# Sch_loapay.net
KiCad netlist of a schematic drawn in Altium Designer
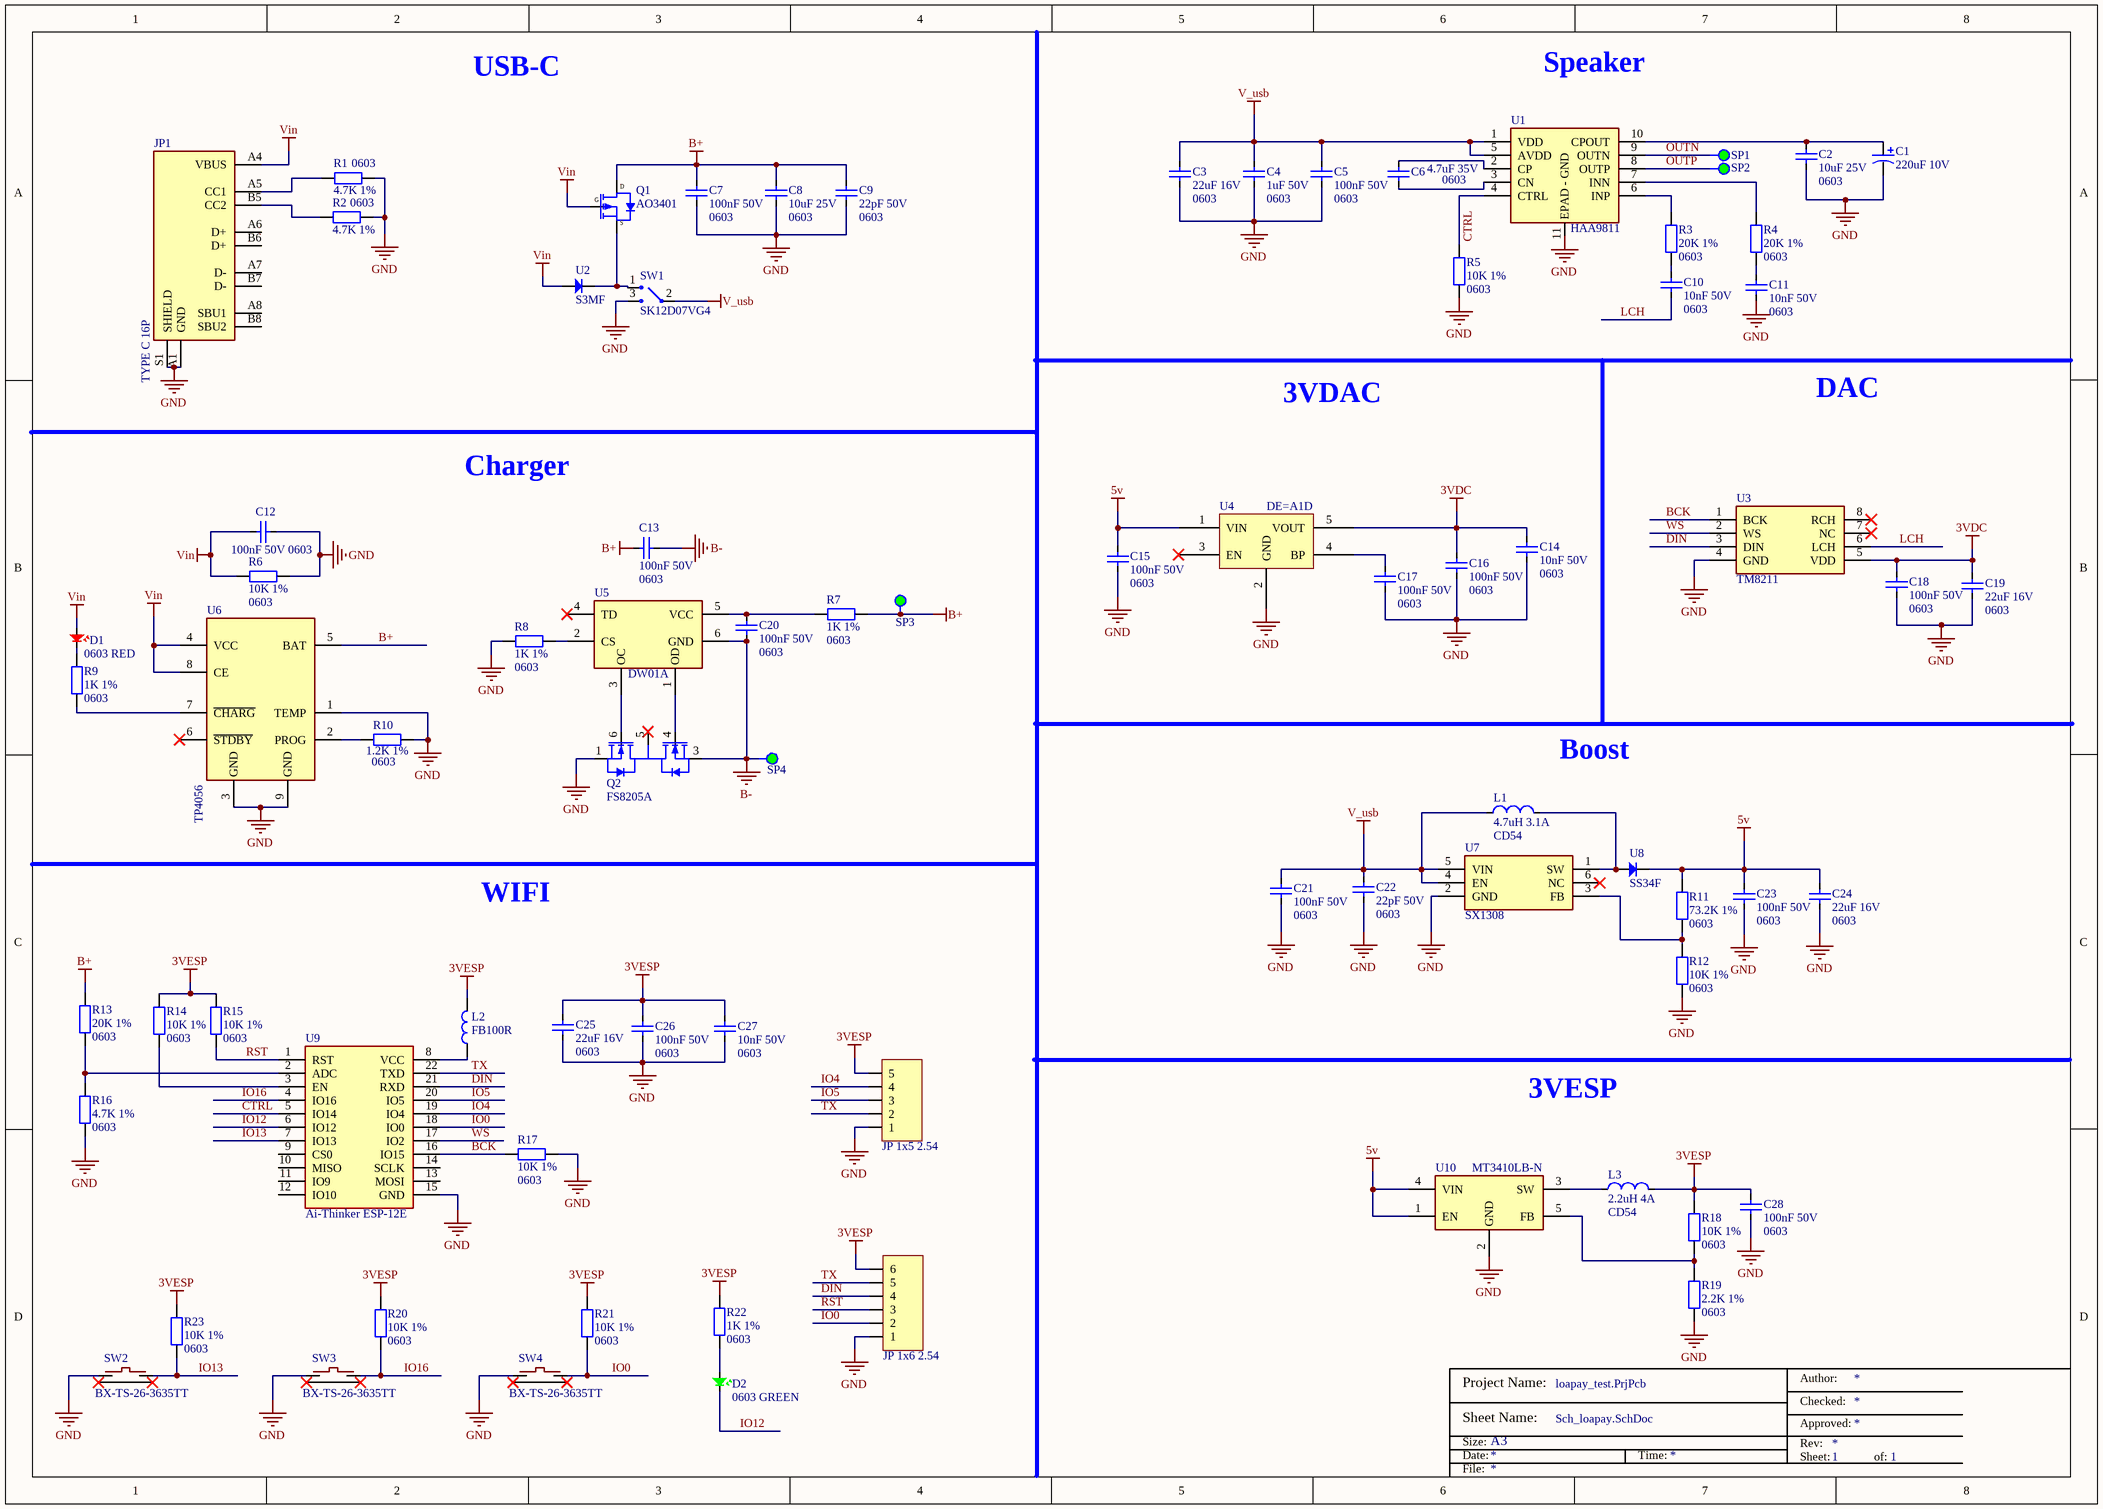
[diagram p0: Sch_loapay.SchDoc]

(export (version "E")
  (design (tool "Eeschema 10.0.6"))
  (components
    (comp (ref "C1")
      (value "220uF 10V")
      (footprint "CAP-ALU-SMD-D-NEW")
      (description "220uF 10V ±20% SMD,D6.3xL7.7mm Aluminum Electrolytic Capacitors - SMD ROHS")
      (fields
        (field (name "MANUFACTURER") "Honor Elec")
        (field (name "MANUFACTURE PART NUMBER") "RVT1A221M0607")
      )
      (libsource (lib "IOT SOLUTIONS LOAPAY V5.5.2") (part "C_ALU_220uF_10V_D"))
    )
    (comp (ref "C2")
      (value "10uF 25V")
      (footprint "C0603")
      (description "25V 10uF X5R ±10% 0603 Multilayer Ceramic Capacitors MLCC - SMD/SMT ROHS")
      (fields
        (field (name "MANUFACTURER") "Murata Electronics")
        (field (name "MANUFACTURE PART NUMBER") "GRM188R61E106KA73D")
        (field (name "PACKAGE") "0603")
      )
      (libsource (lib "IOT SOLUTIONS LOAPAY V5.5.2") (part "C0603_MLCC_10uF_25V"))
    )
    (comp (ref "C3")
      (value "22uF 16V")
      (footprint "C0603")
      (description "16V 22uF X5R ±20% 0603 Multilayer Ceramic Capacitors MLCC - SMD/SMT ROHS")
      (fields
        (field (name "MANUFACTURER") "Samsung Electro-Mechanics")
        (field (name "MANUFACTURE PART NUMBER") "CL10A226MO7JZNC")
        (field (name "PACKAGE") "0603")
      )
      (libsource (lib "IOT SOLUTIONS LOAPAY V5.5.2") (part "C0603_MLCC_22uF_16V"))
    )
    (comp (ref "C4")
      (value "1uF 50V")
      (footprint "C0603")
      (description "1 µF ±10% 50V Ceramic Capacitor X5R 0603 (1608 Metric)")
      (fields
        (field (name "MANUFACTURER") "Murata Electronics")
        (field (name "MANUFACTURE PART NUMBER") "GRT188R61H105KE13D")
        (field (name "PACKAGE") "0603")
      )
      (libsource (lib "IOT SOLUTIONS LOAPAY V5.5.2") (part "C0603_MLCC_1uF_50V"))
    )
    (comp (ref "C5")
      (value "100nF 50V")
      (footprint "C0603")
      (description "50V 100nF X7R ±10% 0603 Multilayer Ceramic Capacitors MLCC - SMD/SMT ROHS")
      (fields
        (field (name "MANUFACTURER") "YAGEO")
        (field (name "MANUFACTURE PART NUMBER") "CC0603KRX7R9BB104")
        (field (name "PACKAGE") "0603")
      )
      (libsource (lib "IOT SOLUTIONS LOAPAY V5.5.2") (part "C0603_MLCC_100nF_50V"))
    )
    (comp (ref "C6")
      (value "4.7uF 35V")
      (footprint "C0603")
      (description "35V 4.7uF X5R ±10% 0603 Multilayer Ceramic Capacitors MLCC - SMD/SMT ROHS")
      (fields
        (field (name "MANUFACTURER") "TDK")
        (field (name "MANUFACTURE PART NUMBER") "C1608X5R1V475KT000E")
        (field (name "PACKAGE") "0603")
      )
      (libsource (lib "IOT SOLUTIONS LOAPAY V5.5.2") (part "C0603_MLCC_4.7uF_35V"))
    )
    (comp (ref "C7")
      (value "100nF 50V")
      (footprint "C0603")
      (description "50V 100nF X7R ±10% 0603 Multilayer Ceramic Capacitors MLCC - SMD/SMT ROHS")
      (fields
        (field (name "MANUFACTURER") "YAGEO")
        (field (name "MANUFACTURE PART NUMBER") "CC0603KRX7R9BB104")
        (field (name "PACKAGE") "0603")
      )
      (libsource (lib "IOT SOLUTIONS LOAPAY V5.5.2") (part "C0603_MLCC_100nF_50V"))
    )
    (comp (ref "C8")
      (value "10uF 25V")
      (footprint "C0603")
      (description "25V 10uF X5R ±10% 0603 Multilayer Ceramic Capacitors MLCC - SMD/SMT ROHS")
      (fields
        (field (name "MANUFACTURER") "Murata Electronics")
        (field (name "MANUFACTURE PART NUMBER") "GRM188R61E106KA73D")
        (field (name "PACKAGE") "0603")
      )
      (libsource (lib "IOT SOLUTIONS LOAPAY V5.5.2") (part "C0603_MLCC_10uF_25V"))
    )
    (comp (ref "C9")
      (value "22pF 50V")
      (footprint "C0603")
      (description "50V 22pF NP0 ±5% 0603 Multilayer Ceramic Capacitors MLCC - SMD/SMT ROHS")
      (fields
        (field (name "MANUFACTURER") "YAGEO")
        (field (name "MANUFACTURE PART NUMBER") "CC0603JRNPO9BN220")
        (field (name "PACKAGE") "0603")
      )
      (libsource (lib "IOT SOLUTIONS LOAPAY V5.5.2") (part "C0603_MLCC_22pF_50V"))
    )
    (comp (ref "C10")
      (value "10nF 50V")
      (footprint "C0603")
      (description "50V 10nF X7R ±10% 0603 Multilayer Ceramic Capacitors MLCC - SMD/SMT ROHS")
      (fields
        (field (name "MANUFACTURER") "YAGEO")
        (field (name "MANUFACTURE PART NUMBER") "CC0603KRX7R9BB103")
        (field (name "PACKAGE") "0603")
      )
      (libsource (lib "IOT SOLUTIONS LOAPAY V5.5.2") (part "C0603_MLCC_10nF_50V"))
    )
    (comp (ref "C11")
      (value "10nF 50V")
      (footprint "C0603")
      (description "50V 10nF X7R ±10% 0603 Multilayer Ceramic Capacitors MLCC - SMD/SMT ROHS")
      (fields
        (field (name "MANUFACTURER") "YAGEO")
        (field (name "MANUFACTURE PART NUMBER") "CC0603KRX7R9BB103")
        (field (name "PACKAGE") "0603")
      )
      (libsource (lib "IOT SOLUTIONS LOAPAY V5.5.2") (part "C0603_MLCC_10nF_50V"))
    )
    (comp (ref "C12")
      (value "100nF 50V")
      (footprint "C0603")
      (description "50V 100nF X7R ±10% 0603 Multilayer Ceramic Capacitors MLCC - SMD/SMT ROHS")
      (fields
        (field (name "MANUFACTURER") "YAGEO")
        (field (name "MANUFACTURE PART NUMBER") "CC0603KRX7R9BB104")
        (field (name "PACKAGE") "0603")
      )
      (libsource (lib "IOT SOLUTIONS LOAPAY V5.5.2") (part "C0603_MLCC_100nF_50V"))
    )
    (comp (ref "C13")
      (value "100nF 50V")
      (footprint "C0603")
      (description "50V 100nF X7R ±10% 0603 Multilayer Ceramic Capacitors MLCC - SMD/SMT ROHS")
      (fields
        (field (name "MANUFACTURER") "YAGEO")
        (field (name "MANUFACTURE PART NUMBER") "CC0603KRX7R9BB104")
        (field (name "PACKAGE") "0603")
      )
      (libsource (lib "IOT SOLUTIONS LOAPAY V5.5.2") (part "C0603_MLCC_100nF_50V"))
    )
    (comp (ref "C14")
      (value "10nF 50V")
      (footprint "C0603")
      (description "50V 10nF X7R ±10% 0603 Multilayer Ceramic Capacitors MLCC - SMD/SMT ROHS")
      (fields
        (field (name "MANUFACTURER") "YAGEO")
        (field (name "MANUFACTURE PART NUMBER") "CC0603KRX7R9BB103")
        (field (name "PACKAGE") "0603")
      )
      (libsource (lib "IOT SOLUTIONS LOAPAY V5.5.2") (part "C0603_MLCC_10nF_50V"))
    )
    (comp (ref "C15")
      (value "100nF 50V")
      (footprint "C0603")
      (description "50V 100nF X7R ±10% 0603 Multilayer Ceramic Capacitors MLCC - SMD/SMT ROHS")
      (fields
        (field (name "MANUFACTURER") "YAGEO")
        (field (name "MANUFACTURE PART NUMBER") "CC0603KRX7R9BB104")
        (field (name "PACKAGE") "0603")
      )
      (libsource (lib "IOT SOLUTIONS LOAPAY V5.5.2") (part "C0603_MLCC_100nF_50V"))
    )
    (comp (ref "C16")
      (value "100nF 50V")
      (footprint "C0603")
      (description "50V 100nF X7R ±10% 0603 Multilayer Ceramic Capacitors MLCC - SMD/SMT ROHS")
      (fields
        (field (name "MANUFACTURER") "YAGEO")
        (field (name "MANUFACTURE PART NUMBER") "CC0603KRX7R9BB104")
        (field (name "PACKAGE") "0603")
      )
      (libsource (lib "IOT SOLUTIONS LOAPAY V5.5.2") (part "C0603_MLCC_100nF_50V"))
    )
    (comp (ref "C17")
      (value "100nF 50V")
      (footprint "C0603")
      (description "50V 100nF X7R ±10% 0603 Multilayer Ceramic Capacitors MLCC - SMD/SMT ROHS")
      (fields
        (field (name "MANUFACTURER") "YAGEO")
        (field (name "MANUFACTURE PART NUMBER") "CC0603KRX7R9BB104")
        (field (name "PACKAGE") "0603")
      )
      (libsource (lib "IOT SOLUTIONS LOAPAY V5.5.2") (part "C0603_MLCC_100nF_50V"))
    )
    (comp (ref "C18")
      (value "100nF 50V")
      (footprint "C0603")
      (description "50V 100nF X7R ±10% 0603 Multilayer Ceramic Capacitors MLCC - SMD/SMT ROHS")
      (fields
        (field (name "MANUFACTURER") "YAGEO")
        (field (name "MANUFACTURE PART NUMBER") "CC0603KRX7R9BB104")
        (field (name "PACKAGE") "0603")
      )
      (libsource (lib "IOT SOLUTIONS LOAPAY V5.5.2") (part "C0603_MLCC_100nF_50V"))
    )
    (comp (ref "C19")
      (value "22uF 16V")
      (footprint "C0603")
      (description "16V 22uF X5R ±20% 0603 Multilayer Ceramic Capacitors MLCC - SMD/SMT ROHS")
      (fields
        (field (name "MANUFACTURER") "Samsung Electro-Mechanics")
        (field (name "MANUFACTURE PART NUMBER") "CL10A226MO7JZNC")
        (field (name "PACKAGE") "0603")
      )
      (libsource (lib "IOT SOLUTIONS LOAPAY V5.5.2") (part "C0603_MLCC_22uF_16V"))
    )
    (comp (ref "C20")
      (value "100nF 50V")
      (footprint "C0603")
      (description "50V 100nF X7R ±10% 0603 Multilayer Ceramic Capacitors MLCC - SMD/SMT ROHS")
      (fields
        (field (name "MANUFACTURER") "YAGEO")
        (field (name "MANUFACTURE PART NUMBER") "CC0603KRX7R9BB104")
        (field (name "PACKAGE") "0603")
      )
      (libsource (lib "IOT SOLUTIONS LOAPAY V5.5.2") (part "C0603_MLCC_100nF_50V"))
    )
    (comp (ref "C21")
      (value "100nF 50V")
      (footprint "C0603")
      (description "50V 100nF X7R ±10% 0603 Multilayer Ceramic Capacitors MLCC - SMD/SMT ROHS")
      (fields
        (field (name "MANUFACTURER") "YAGEO")
        (field (name "MANUFACTURE PART NUMBER") "CC0603KRX7R9BB104")
        (field (name "PACKAGE") "0603")
      )
      (libsource (lib "IOT SOLUTIONS LOAPAY V5.5.2") (part "C0603_MLCC_100nF_50V"))
    )
    (comp (ref "C22")
      (value "22pF 50V")
      (footprint "C0603")
      (description "50V 22pF NP0 ±5% 0603 Multilayer Ceramic Capacitors MLCC - SMD/SMT ROHS")
      (fields
        (field (name "MANUFACTURER") "YAGEO")
        (field (name "MANUFACTURE PART NUMBER") "CC0603JRNPO9BN220")
        (field (name "PACKAGE") "0603")
      )
      (libsource (lib "IOT SOLUTIONS LOAPAY V5.5.2") (part "C0603_MLCC_22pF_50V"))
    )
    (comp (ref "C23")
      (value "100nF 50V")
      (footprint "C0603")
      (description "50V 100nF X7R ±10% 0603 Multilayer Ceramic Capacitors MLCC - SMD/SMT ROHS")
      (fields
        (field (name "MANUFACTURER") "YAGEO")
        (field (name "MANUFACTURE PART NUMBER") "CC0603KRX7R9BB104")
        (field (name "PACKAGE") "0603")
      )
      (libsource (lib "IOT SOLUTIONS LOAPAY V5.5.2") (part "C0603_MLCC_100nF_50V"))
    )
    (comp (ref "C24")
      (value "22uF 16V")
      (footprint "C0603")
      (description "16V 22uF X5R ±20% 0603 Multilayer Ceramic Capacitors MLCC - SMD/SMT ROHS")
      (fields
        (field (name "MANUFACTURER") "Samsung Electro-Mechanics")
        (field (name "MANUFACTURE PART NUMBER") "CL10A226MO7JZNC")
        (field (name "PACKAGE") "0603")
      )
      (libsource (lib "IOT SOLUTIONS LOAPAY V5.5.2") (part "C0603_MLCC_22uF_16V"))
    )
    (comp (ref "C25")
      (value "22uF 16V")
      (footprint "C0603")
      (description "16V 22uF X5R ±20% 0603 Multilayer Ceramic Capacitors MLCC - SMD/SMT ROHS")
      (fields
        (field (name "MANUFACTURER") "Samsung Electro-Mechanics")
        (field (name "MANUFACTURE PART NUMBER") "CL10A226MO7JZNC")
        (field (name "PACKAGE") "0603")
      )
      (libsource (lib "IOT SOLUTIONS LOAPAY V5.5.2") (part "C0603_MLCC_22uF_16V"))
    )
    (comp (ref "C26")
      (value "100nF 50V")
      (footprint "C0603")
      (description "50V 100nF X7R ±10% 0603 Multilayer Ceramic Capacitors MLCC - SMD/SMT ROHS")
      (fields
        (field (name "MANUFACTURER") "YAGEO")
        (field (name "MANUFACTURE PART NUMBER") "CC0603KRX7R9BB104")
        (field (name "PACKAGE") "0603")
      )
      (libsource (lib "IOT SOLUTIONS LOAPAY V5.5.2") (part "C0603_MLCC_100nF_50V"))
    )
    (comp (ref "C27")
      (value "10nF 50V")
      (footprint "C0603")
      (description "50V 10nF X7R ±10% 0603 Multilayer Ceramic Capacitors MLCC - SMD/SMT ROHS")
      (fields
        (field (name "MANUFACTURER") "YAGEO")
        (field (name "MANUFACTURE PART NUMBER") "CC0603KRX7R9BB103")
        (field (name "PACKAGE") "0603")
      )
      (libsource (lib "IOT SOLUTIONS LOAPAY V5.5.2") (part "C0603_MLCC_10nF_50V"))
    )
    (comp (ref "C28")
      (value "100nF 50V")
      (footprint "C0603")
      (description "50V 100nF X7R ±10% 0603 Multilayer Ceramic Capacitors MLCC - SMD/SMT ROHS")
      (fields
        (field (name "MANUFACTURER") "YAGEO")
        (field (name "MANUFACTURE PART NUMBER") "CC0603KRX7R9BB104")
        (field (name "PACKAGE") "0603")
      )
      (libsource (lib "IOT SOLUTIONS LOAPAY V5.5.2") (part "C0603_MLCC_100nF_50V"))
    )
    (comp (ref "D1")
      (value "0603 RED")
      (footprint "LED0603_RED")
      (fields
        (field (name "MANUFACTURER") "XINGLIGHT")
        (field (name "MANUFACTURE PART NUMBER") "XL-1608SURC-06")
      )
      (libsource (lib "IOT SOLUTIONS LOAPAY V5.5.2") (part "L0603_RED"))
    )
    (comp (ref "D2")
      (value "0603 GREEN")
      (footprint "LED0603_GREEN")
      (fields
        (field (name "MANUFACTURER") "Amicc")
        (field (name "MANUFACTURE PART NUMBER") "A-SP192DGHC-C01-4T")
      )
      (libsource (lib "IOT SOLUTIONS LOAPAY V5.5.2") (part "L0603_GREEN"))
    )
    (comp (ref "JP1")
      (value "TYPE C 16P")
      (footprint "TYPE C 16P")
      (fields
        (field (name "MANUFACTURER") "Amphenol ICC (Commercial Products)")
        (field (name "MANUFACTURE PART NUMBER") "12402012E212A")
      )
      (libsource (lib "IOT SOLUTIONS LOAPAY V5.5.2") (part "TYPE_C_16P"))
    )
    (comp (ref "JP2")
      (value "JP 1x5 2.54")
      (footprint "JP 1x5 DT")
      (description "Cắm")
      (libsource (lib "Altium_Lib_by_KhueNguyenCreator") (part "JP 1x5 2.54 Duc Thang"))
    )
    (comp (ref "JP3")
      (value "JP 1x6 2.54")
      (footprint "JP 1x6 DT")
      (description "Cắm")
      (libsource (lib "Altium_Lib_by_KhueNguyenCreator") (part "JP 1x6 2.54 Duc Thang"))
    )
    (comp (ref "L1")
      (value "4.7uH 3.1A")
      (footprint "CD54")
      (description "3.1A 4.7uH ±20% SMD,5.8x5.2mm Power Inductors ROHS")
      (fields
        (field (name "MANUFACTURER") "Ceaiya")
        (field (name "MANUFACTURE PART NUMBER") "CD54-4R7M")
        (field (name "PACKAGE") "CD54")
      )
      (libsource (lib "IOT SOLUTIONS LOAPAY V5.5.2") (part "CD54_4.7uH_3.1A"))
    )
    (comp (ref "L2")
      (value "FB100R")
      (footprint "L-INDUCTOR 1206")
      (libsource (lib "IO84C124LR") (part "L-Inductor"))
    )
    (comp (ref "L3")
      (value "2.2uH 4A")
      (footprint "CD54")
      (description "4A 2.2uH ±20% SMD,5.8x5.2mm Power Inductors ROHS")
      (fields
        (field (name "MANUFACTURER") "Ceaiya")
        (field (name "MANUFACTURE PART NUMBER") "CD54-2R2M")
        (field (name "PACKAGE") "CD54")
      )
      (libsource (lib "IOT SOLUTIONS LOAPAY V5.5.2") (part "CD54_2.2uH_4A"))
    )
    (comp (ref "Q1")
      (value "AO3401")
      (footprint "SOT-23-3")
      (description "30V 4.2A 42mΩ@10V,4A 1.4W 800mV@250uA 1 Piece P-Channel SOT-23 MOSFETs ROHS")
      (fields (field (name "MANUFACTURER") "ElecSuper"))
      (libsource (lib "IOT SOLUTIONS LOAPAY V5.5.2") (part "AO3401"))
    )
    (comp (ref "Q2")
      (value "FS8205A")
      (footprint "SOT23-6")
      (description "20V 25mΩ@2.5V,3A 1.5W 500mV SOT-23-6 MOSFETs ROHS")
      (fields (field (name "MANUFACTURER") "TECH PUBLIC"))
      (libsource (lib "IOT SOLUTIONS LOAPAY V5.5.2") (part "FS8205A"))
    )
    (comp (ref "R1")
      (value "4.7K 1%")
      (footprint "RES_SMD_0603")
      (description "4.7 kOhms ±1% 0.1W, 1/10W Chip Resistor 0603 (1608 Metric) Moisture Resistant Thick Film")
      (fields
        (field (name "MANUFACTURER") "YAGEO")
        (field (name "MANUFACTURE PART NUMBER") "RC0603FR-074K7L")
        (field (name "PACKAGE") "0603")
      )
      (libsource (lib "IOT SOLUTIONS LOAPAY V5.5.2") (part "R0603_4.7K"))
    )
    (comp (ref "R2")
      (value "4.7K 1%")
      (footprint "RES_SMD_0603")
      (description "4.7 kOhms ±1% 0.1W, 1/10W Chip Resistor 0603 (1608 Metric) Moisture Resistant Thick Film")
      (fields
        (field (name "MANUFACTURER") "YAGEO")
        (field (name "MANUFACTURE PART NUMBER") "RC0603FR-074K7L")
        (field (name "PACKAGE") "0603")
      )
      (libsource (lib "IOT SOLUTIONS LOAPAY V5.5.2") (part "R0603_4.7K"))
    )
    (comp (ref "R3")
      (value "20K 1%")
      (footprint "RES_SMD_0603")
      (description "20 kOhms ±1% 0.063W, 1/16W Chip Resistor 0402 (1005 Metric) Moisture Resistant Thick Film")
      (fields
        (field (name "MANUFACTURER") "YAGEO")
        (field (name "MANUFACTURE PART NUMBER") "RC0805FR-0720KL")
        (field (name "PACKAGE") "0603")
      )
      (libsource (lib "IOT SOLUTIONS LOAPAY V5.5.2") (part "R0603_20K"))
    )
    (comp (ref "R4")
      (value "20K 1%")
      (footprint "RES_SMD_0603")
      (description "20 kOhms ±1% 0.063W, 1/16W Chip Resistor 0402 (1005 Metric) Moisture Resistant Thick Film")
      (fields
        (field (name "MANUFACTURER") "YAGEO")
        (field (name "MANUFACTURE PART NUMBER") "RC0805FR-0720KL")
        (field (name "PACKAGE") "0603")
      )
      (libsource (lib "IOT SOLUTIONS LOAPAY V5.5.2") (part "R0603_20K"))
    )
    (comp (ref "R5")
      (value "10K 1%")
      (footprint "RES_SMD_0603")
      (description "10 kOhms ±1% 0.1W, 1/10W Chip Resistor 0603 (1608 Metric) Moisture Resistant Thick Film")
      (fields
        (field (name "MANUFACTURER") "YAGEO")
        (field (name "MANUFACTURE PART NUMBER") "RC0603FR-0710KL")
        (field (name "PACKAGE") "0603")
      )
      (libsource (lib "IOT SOLUTIONS LOAPAY V5.5.2") (part "R0603_10K"))
    )
    (comp (ref "R6")
      (value "10K 1%")
      (footprint "RES_SMD_0603")
      (description "10 kOhms ±1% 0.1W, 1/10W Chip Resistor 0603 (1608 Metric) Moisture Resistant Thick Film")
      (fields
        (field (name "MANUFACTURER") "YAGEO")
        (field (name "MANUFACTURE PART NUMBER") "RC0603FR-0710KL")
        (field (name "PACKAGE") "0603")
      )
      (libsource (lib "IOT SOLUTIONS LOAPAY V5.5.2") (part "R0603_10K"))
    )
    (comp (ref "R7")
      (value "1K 1%")
      (footprint "RES_SMD_0603")
      (description "1 kOhms ±1% 0.1W, 1/10W Chip Resistor 0603 (1608 Metric) Moisture Resistant Thick Film")
      (fields
        (field (name "MANUFACTURER") "YAGEO")
        (field (name "MANUFACTURE PART NUMBER") "RC0603FR-071KL")
        (field (name "PACKAGE") "0603")
      )
      (libsource (lib "IOT SOLUTIONS LOAPAY V5.5.2") (part "R0603_1K"))
    )
    (comp (ref "R8")
      (value "1K 1%")
      (footprint "RES_SMD_0603")
      (description "1 kOhms ±1% 0.1W, 1/10W Chip Resistor 0603 (1608 Metric) Moisture Resistant Thick Film")
      (fields
        (field (name "MANUFACTURER") "YAGEO")
        (field (name "MANUFACTURE PART NUMBER") "RC0603FR-071KL")
        (field (name "PACKAGE") "0603")
      )
      (libsource (lib "IOT SOLUTIONS LOAPAY V5.5.2") (part "R0603_1K"))
    )
    (comp (ref "R9")
      (value "1K 1%")
      (footprint "RES_SMD_0603")
      (description "1 kOhms ±1% 0.1W, 1/10W Chip Resistor 0603 (1608 Metric) Moisture Resistant Thick Film")
      (fields
        (field (name "MANUFACTURER") "YAGEO")
        (field (name "MANUFACTURE PART NUMBER") "RC0603FR-071KL")
        (field (name "PACKAGE") "0603")
      )
      (libsource (lib "IOT SOLUTIONS LOAPAY V5.5.2") (part "R0603_1K"))
    )
    (comp (ref "R10")
      (value "1.2K 1%")
      (footprint "RES_SMD_0603")
      (description "1.2 kOhms ±1% 0.1W, 1/10W Chip Resistor 0603 (1608 Metric) Moisture Resistant Thick Film")
      (fields
        (field (name "MANUFACTURER") "YAGEO")
        (field (name "MANUFACTURE PART NUMBER") "RC0603FR-071K2L")
        (field (name "PACKAGE") "0603")
      )
      (libsource (lib "IOT SOLUTIONS LOAPAY V5.5.2") (part "R0603_1.2K"))
    )
    (comp (ref "R11")
      (value "73.2K 1%")
      (footprint "RES_SMD_0603")
      (description "73.2 kOhms ±1% 0.1W, 1/10W Chip Resistor 0603 (1608 Metric) Moisture Resistant Thick Film")
      (fields
        (field (name "MANUFACTURER") "YAGEO")
        (field (name "MANUFACTURE PART NUMBER") "RC0603FR-0773K2L")
        (field (name "PACKAGE") "0603")
      )
      (libsource (lib "IOT SOLUTIONS LOAPAY V5.5.2") (part "R0603_73.2K"))
    )
    (comp (ref "R12")
      (value "10K 1%")
      (footprint "RES_SMD_0603")
      (description "10 kOhms ±1% 0.1W, 1/10W Chip Resistor 0603 (1608 Metric) Moisture Resistant Thick Film")
      (fields
        (field (name "MANUFACTURER") "YAGEO")
        (field (name "MANUFACTURE PART NUMBER") "RC0603FR-0710KL")
        (field (name "PACKAGE") "0603")
      )
      (libsource (lib "IOT SOLUTIONS LOAPAY V5.5.2") (part "R0603_10K"))
    )
    (comp (ref "R13")
      (value "20K 1%")
      (footprint "RES_SMD_0603")
      (description "20 kOhms ±1% 0.063W, 1/16W Chip Resistor 0402 (1005 Metric) Moisture Resistant Thick Film")
      (fields
        (field (name "MANUFACTURER") "YAGEO")
        (field (name "MANUFACTURE PART NUMBER") "RC0805FR-0720KL")
        (field (name "PACKAGE") "0603")
      )
      (libsource (lib "IOT SOLUTIONS LOAPAY V5.5.2") (part "R0603_20K"))
    )
    (comp (ref "R14")
      (value "10K 1%")
      (footprint "RES_SMD_0603")
      (description "10 kOhms ±1% 0.1W, 1/10W Chip Resistor 0603 (1608 Metric) Moisture Resistant Thick Film")
      (fields
        (field (name "MANUFACTURER") "YAGEO")
        (field (name "MANUFACTURE PART NUMBER") "RC0603FR-0710KL")
        (field (name "PACKAGE") "0603")
      )
      (libsource (lib "IOT SOLUTIONS LOAPAY V5.5.2") (part "R0603_10K"))
    )
    (comp (ref "R15")
      (value "10K 1%")
      (footprint "RES_SMD_0603")
      (description "10 kOhms ±1% 0.1W, 1/10W Chip Resistor 0603 (1608 Metric) Moisture Resistant Thick Film")
      (fields
        (field (name "MANUFACTURER") "YAGEO")
        (field (name "MANUFACTURE PART NUMBER") "RC0603FR-0710KL")
        (field (name "PACKAGE") "0603")
      )
      (libsource (lib "IOT SOLUTIONS LOAPAY V5.5.2") (part "R0603_10K"))
    )
    (comp (ref "R16")
      (value "4.7K 1%")
      (footprint "RES_SMD_0603")
      (description "4.7 kOhms ±1% 0.1W, 1/10W Chip Resistor 0603 (1608 Metric) Moisture Resistant Thick Film")
      (fields
        (field (name "MANUFACTURER") "YAGEO")
        (field (name "MANUFACTURE PART NUMBER") "RC0603FR-074K7L")
        (field (name "PACKAGE") "0603")
      )
      (libsource (lib "IOT SOLUTIONS LOAPAY V5.5.2") (part "R0603_4.7K"))
    )
    (comp (ref "R17")
      (value "10K 1%")
      (footprint "RES_SMD_0603")
      (description "10 kOhms ±1% 0.1W, 1/10W Chip Resistor 0603 (1608 Metric) Moisture Resistant Thick Film")
      (fields
        (field (name "MANUFACTURER") "YAGEO")
        (field (name "MANUFACTURE PART NUMBER") "RC0603FR-0710KL")
        (field (name "PACKAGE") "0603")
      )
      (libsource (lib "IOT SOLUTIONS LOAPAY V5.5.2") (part "R0603_10K"))
    )
    (comp (ref "R18")
      (value "10K 1%")
      (footprint "RES_SMD_0603")
      (description "10 kOhms ±1% 0.1W, 1/10W Chip Resistor 0603 (1608 Metric) Moisture Resistant Thick Film")
      (fields
        (field (name "MANUFACTURER") "YAGEO")
        (field (name "MANUFACTURE PART NUMBER") "RC0603FR-0710KL")
        (field (name "PACKAGE") "0603")
      )
      (libsource (lib "IOT SOLUTIONS LOAPAY V5.5.2") (part "R0603_10K"))
    )
    (comp (ref "R19")
      (value "2.2K 1%")
      (footprint "RES_SMD_0603")
      (description "2.2 kOhms ±1% 0.1W, 1/10W Chip Resistor 0603 (1608 Metric) Moisture Resistant Thick Film")
      (fields
        (field (name "MANUFACTURER") "YAGEO")
        (field (name "MANUFACTURE PART NUMBER") "RC0603FR-072K2L")
        (field (name "PACKAGE") "0603")
      )
      (libsource (lib "IOT SOLUTIONS LOAPAY V5.5.2") (part "R0603_2.2K"))
    )
    (comp (ref "R20")
      (value "10K 1%")
      (footprint "RES_SMD_0603")
      (description "10 kOhms ±1% 0.1W, 1/10W Chip Resistor 0603 (1608 Metric) Moisture Resistant Thick Film")
      (fields
        (field (name "MANUFACTURER") "YAGEO")
        (field (name "MANUFACTURE PART NUMBER") "RC0603FR-0710KL")
        (field (name "PACKAGE") "0603")
      )
      (libsource (lib "IOT SOLUTIONS LOAPAY V5.5.2") (part "R0603_10K"))
    )
    (comp (ref "R21")
      (value "10K 1%")
      (footprint "RES_SMD_0603")
      (description "10 kOhms ±1% 0.1W, 1/10W Chip Resistor 0603 (1608 Metric) Moisture Resistant Thick Film")
      (fields
        (field (name "MANUFACTURER") "YAGEO")
        (field (name "MANUFACTURE PART NUMBER") "RC0603FR-0710KL")
        (field (name "PACKAGE") "0603")
      )
      (libsource (lib "IOT SOLUTIONS LOAPAY V5.5.2") (part "R0603_10K"))
    )
    (comp (ref "R22")
      (value "1K 1%")
      (footprint "RES_SMD_0603")
      (description "1 kOhms ±1% 0.1W, 1/10W Chip Resistor 0603 (1608 Metric) Moisture Resistant Thick Film")
      (fields
        (field (name "MANUFACTURER") "YAGEO")
        (field (name "MANUFACTURE PART NUMBER") "RC0603FR-071KL")
        (field (name "PACKAGE") "0603")
      )
      (libsource (lib "IOT SOLUTIONS LOAPAY V5.5.2") (part "R0603_1K"))
    )
    (comp (ref "R23")
      (value "10K 1%")
      (footprint "RES_SMD_0603")
      (description "10 kOhms ±1% 0.1W, 1/10W Chip Resistor 0603 (1608 Metric) Moisture Resistant Thick Film")
      (fields
        (field (name "MANUFACTURER") "YAGEO")
        (field (name "MANUFACTURE PART NUMBER") "RC0603FR-0710KL")
        (field (name "PACKAGE") "0603")
      )
      (libsource (lib "IOT SOLUTIONS LOAPAY V5.5.2") (part "R0603_10K"))
    )
    (comp (ref "SP1")
      (value "SP")
      (footprint "SOLDERING PAD BIG 2")
      (description "Soldering Pad")
      (libsource (lib "IOT SOLUTIONS LOAPAY V5.5.2") (part "SOLDERING PAD"))
    )
    (comp (ref "SP2")
      (value "SP")
      (footprint "SOLDERING PAD BIG 2")
      (description "Soldering Pad")
      (libsource (lib "IOT SOLUTIONS LOAPAY V5.5.2") (part "SOLDERING PAD"))
    )
    (comp (ref "SP3")
      (value "SP")
      (footprint "SOLDERING PAD BIG 2")
      (description "Soldering Pad")
      (libsource (lib "IOT SOLUTIONS LOAPAY V5.5.2") (part "SOLDERING PAD"))
    )
    (comp (ref "SP4")
      (value "SP")
      (footprint "SOLDERING PAD BIG 2")
      (description "Soldering Pad")
      (libsource (lib "IOT SOLUTIONS LOAPAY V5.5.2") (part "SOLDERING PAD"))
    )
    (comp (ref "SW1")
      (value "SK12D07VG4")
      (footprint "SK12D07VG4")
      (description "500mA SPDT 50V 5千次 Plugin Slide Switches ROHS")
      (fields (field (name "MANUFACTURER") "SHOU HAN"))
      (libsource (lib "IOT SOLUTIONS LOAPAY V5.5.2") (part "SK12D07VG4"))
    )
    (comp (ref "SW2")
      (value "BX-TS-26-3635TT")
      (footprint "BX-TS-26-3635TT")
      (fields (field (name "MANUFACTURER") "Bossie") (field (name "MANUFACTURE PART NUMBER") "C18078107"))
      (libsource (lib "IOT SOLUTIONS LOAPAY V5.5.2") (part "BX-TS-26-3635TT"))
    )
    (comp (ref "SW3")
      (value "BX-TS-26-3635TT")
      (footprint "BX-TS-26-3635TT")
      (fields (field (name "MANUFACTURER") "Bossie") (field (name "MANUFACTURE PART NUMBER") "C18078107"))
      (libsource (lib "IOT SOLUTIONS LOAPAY V5.5.2") (part "BX-TS-26-3635TT"))
    )
    (comp (ref "SW4")
      (value "BX-TS-26-3635TT")
      (footprint "BX-TS-26-3635TT")
      (fields (field (name "MANUFACTURER") "Bossie") (field (name "MANUFACTURE PART NUMBER") "C18078107"))
      (libsource (lib "IOT SOLUTIONS LOAPAY V5.5.2") (part "BX-TS-26-3635TT"))
    )
    (comp (ref "U1")
      (value "HAA9811")
      (footprint "ESOP-10")
      (description "Amplifier")
      (fields (field (name "MANUFACTURER") "ChipSourceTek Technology"))
      (libsource (lib "IOT SOLUTIONS LOAPAY V5.5.2") (part "HAA9811"))
    )
    (comp (ref "U2")
      (value "S3MF")
      (footprint "SMAF_L3.5-W2.6-LS4.7-RD")
      (description "3A Independent Type 1.1V@3A 1kV SMAF Diodes - General Purpose ROHS")
      (fields (field (name "MANUFACTURER") "Shandong Jingdao Microelectronics"))
      (libsource (lib "IOT SOLUTIONS LOAPAY V5.5.2") (part "S3MF"))
    )
    (comp (ref "U3")
      (value "TM8211")
      (footprint "SOIC-8")
      (description "3V~8V 16-Bit SOIC-8 Digital to Analog Converters (DAC) ROHS")
      (fields (field (name "MANUFACTURER") "TM(Shenzhen Titan Micro Elec)"))
      (libsource (lib "IOT SOLUTIONS LOAPAY V5.5.2") (part "TM8211"))
    )
    (comp (ref "U4")
      (value "DE=A1D")
      (footprint "SOT95P260X135-5N")
      (description "RT9193 on ap")
      (libsource (lib "quyybinh") (part "DE=A1D"))
    )
    (comp (ref "U5")
      (value "DW01A")
      (footprint "SOT23-6")
      (description "1V~5.5V SOT-23-6 Battery Management ROHS")
      (fields (field (name "MANUFACTURER") "PJSEMI"))
      (libsource (lib "IOT SOLUTIONS LOAPAY V5.5.2") (part "DW01A"))
    )
    (comp (ref "U6")
      (value "TP4056")
      (footprint "ESOP-8")
      (description "ESOP-8 Battery Management ICs ROHS")
      (fields (field (name "MANUFACTURER") "MSKSEMI") (field (name "MANUFACTURE PART NUMBER") "TP4056-MS"))
      (libsource (lib "IOT SOLUTIONS LOAPAY V5.5.2") (part "TP4056"))
    )
    (comp (ref "U7")
      (value "SX1308")
      (footprint "SOT23-6")
      (description "Boost type Adjustable 28V 2A 2V~24V SOT-23-6 DC-DC Converters ROHS")
      (fields (field (name "MANUFACTURER") "SX(Shenzhen Suosemi Tech)"))
      (libsource (lib "IOT SOLUTIONS LOAPAY V5.5.2") (part "SX1308"))
    )
    (comp (ref "U8")
      (value "SS34F")
      (footprint "SMAF_L3.5-W2.6-LS4.7-RD")
      (description "40V Independent Type 3A 700mV@3A SMAF Schottky Diodes ROHS")
      (fields (field (name "MANUFACTURER") "HXY MOSFET"))
      (libsource (lib "IOT SOLUTIONS LOAPAY V5.5.2") (part "SS34F"))
    )
    (comp (ref "U9")
      (value "Ai-Thinker ESP-12E")
      (footprint "ESP8266-12E")
      (description "-90dBm 16dBm ESP8266 chip On-board PCB antenna 2.4GHz SMD,16x24mm WiFi Modules ROHS")
      (fields (field (name "MANUFACTURER") "Ai-Thinker") (field (name "MANUFACTURE PART NUMBER") "ESP-12E"))
      (libsource (lib "IOT SOLUTIONS LOAPAY V5.5.2") (part "Ai-Thinker ESP-12E"))
    )
    (comp (ref "U10")
      (value "MT3410LB-N")
      (footprint "SOT23_5")
      (description "SOT-23-5 DC-DC Converters ROHS")
      (fields (field (name "MANUFACTURER") "XI'AN Aerosemi Tech"))
      (libsource (lib "IOT SOLUTIONS LOAPAY V5.5.2") (part "MT3410LB-N"))
    )
  )
  (nets
    (net (code "1") (name "/BCK") (class "Default")
      (node (ref "R17") (pin "2") (pinfunction "2_2") (pintype "passive"))
      (node (ref "U3") (pin "1") (pinfunction "BCK_1") (pintype "passive"))
      (node (ref "U9") (pin "16") (pinfunction "IO15_16") (pintype "passive"))
    )
    (net (code "2") (name "/CTRL") (class "Default")
      (node (ref "R5") (pin "2") (pinfunction "2_2") (pintype "passive"))
      (node (ref "U1") (pin "4") (pinfunction "CTRL_4") (pintype "passive"))
      (node (ref "U9") (pin "5") (pinfunction "IO14_5") (pintype "passive"))
    )
    (net (code "3") (name "/DIN") (class "Default")
      (node (ref "JP3") (pin "4") (pinfunction "4_4") (pintype "passive"))
      (node (ref "U3") (pin "3") (pinfunction "DIN_3") (pintype "passive"))
      (node (ref "U9") (pin "21") (pinfunction "RXD_21") (pintype "passive"))
    )
    (net (code "4") (name "/IO0") (class "Default")
      (node (ref "JP3") (pin "2") (pinfunction "2_2") (pintype "passive"))
      (node (ref "R21") (pin "2") (pinfunction "2_2") (pintype "passive"))
      (node (ref "SW4") (pin "2") (pinfunction "2_2") (pintype "passive"))
      (node (ref "U9") (pin "18") (pinfunction "IO0_18") (pintype "passive"))
    )
    (net (code "5") (name "/IO4") (class "Default")
      (node (ref "JP2") (pin "4") (pinfunction "4_4") (pintype "passive"))
      (node (ref "U9") (pin "19") (pinfunction "IO4_19") (pintype "passive"))
    )
    (net (code "6") (name "/IO5") (class "Default")
      (node (ref "JP2") (pin "3") (pinfunction "3_3") (pintype "passive"))
      (node (ref "U9") (pin "20") (pinfunction "IO5_20") (pintype "passive"))
    )
    (net (code "7") (name "/IO12") (class "Default")
      (node (ref "D2") (pin "2") (pinfunction "2_2") (pintype "passive"))
      (node (ref "U9") (pin "6") (pinfunction "IO12_6") (pintype "passive"))
    )
    (net (code "8") (name "/IO13") (class "Default")
      (node (ref "R23") (pin "2") (pinfunction "2_2") (pintype "passive"))
      (node (ref "SW2") (pin "2") (pinfunction "2_2") (pintype "passive"))
      (node (ref "U9") (pin "7") (pinfunction "IO13_7") (pintype "passive"))
    )
    (net (code "9") (name "/IO16") (class "Default")
      (node (ref "R20") (pin "2") (pinfunction "2_2") (pintype "passive"))
      (node (ref "SW3") (pin "2") (pinfunction "2_2") (pintype "passive"))
      (node (ref "U9") (pin "4") (pinfunction "IO16_4") (pintype "passive"))
    )
    (net (code "10") (name "/LCH") (class "Default")
      (node (ref "C10") (pin "1") (pinfunction "1_1") (pintype "passive"))
      (node (ref "U3") (pin "6") (pinfunction "LCH_6") (pintype "passive"))
    )
    (net (code "11") (name "/OUTN") (class "Default")
      (node (ref "SP1") (pin "1") (pinfunction "1_1") (pintype "passive"))
      (node (ref "U1") (pin "9") (pinfunction "OUTN_9") (pintype "passive"))
    )
    (net (code "12") (name "/OUTP") (class "Default")
      (node (ref "SP2") (pin "1") (pinfunction "1_1") (pintype "passive"))
      (node (ref "U1") (pin "8") (pinfunction "OUTP_8") (pintype "passive"))
    )
    (net (code "13") (name "/RST") (class "Default")
      (node (ref "JP3") (pin "3") (pinfunction "3_3") (pintype "passive"))
      (node (ref "R15") (pin "2") (pinfunction "2_2") (pintype "passive"))
      (node (ref "U9") (pin "1") (pinfunction "RST_1") (pintype "passive"))
    )
    (net (code "14") (name "/TX") (class "Default")
      (node (ref "JP2") (pin "2") (pinfunction "2_2") (pintype "passive"))
      (node (ref "JP3") (pin "5") (pinfunction "5_5") (pintype "passive"))
      (node (ref "U9") (pin "22") (pinfunction "TXD_22") (pintype "passive"))
    )
    (net (code "15") (name "/WS") (class "Default")
      (node (ref "U3") (pin "2") (pinfunction "WS_2") (pintype "passive"))
      (node (ref "U9") (pin "17") (pinfunction "IO2_17") (pintype "passive"))
    )
    (net (code "16") (name "3VDC") (class "Default")
      (node (ref "C14") (pin "2") (pinfunction "2_2") (pintype "passive"))
      (node (ref "C16") (pin "2") (pinfunction "2_2") (pintype "passive"))
      (node (ref "C18") (pin "2") (pinfunction "2_2") (pintype "passive"))
      (node (ref "C19") (pin "2") (pinfunction "2_2") (pintype "passive"))
      (node (ref "U3") (pin "5") (pinfunction "VDD_5") (pintype "passive"))
      (node (ref "U4") (pin "5") (pinfunction "VOUT_5") (pintype "passive"))
    )
    (net (code "17") (name "3VESP") (class "Default")
      (node (ref "C25") (pin "2") (pinfunction "2_2") (pintype "passive"))
      (node (ref "C26") (pin "2") (pinfunction "2_2") (pintype "passive"))
      (node (ref "C27") (pin "2") (pinfunction "2_2") (pintype "passive"))
      (node (ref "C28") (pin "2") (pinfunction "2_2") (pintype "passive"))
      (node (ref "JP2") (pin "5") (pinfunction "5_5") (pintype "passive"))
      (node (ref "JP3") (pin "6") (pinfunction "6_6") (pintype "passive"))
      (node (ref "L2") (pin "2") (pinfunction "2_2") (pintype "passive"))
      (node (ref "L3") (pin "2") (pinfunction "2_2") (pintype "passive"))
      (node (ref "R14") (pin "1") (pinfunction "1_1") (pintype "passive"))
      (node (ref "R15") (pin "1") (pinfunction "1_1") (pintype "passive"))
      (node (ref "R18") (pin "2") (pinfunction "2_2") (pintype "passive"))
      (node (ref "R20") (pin "1") (pinfunction "1_1") (pintype "passive"))
      (node (ref "R21") (pin "1") (pinfunction "1_1") (pintype "passive"))
      (node (ref "R22") (pin "2") (pinfunction "2_2") (pintype "passive"))
      (node (ref "R23") (pin "1") (pinfunction "1_1") (pintype "passive"))
    )
    (net (code "18") (name "5v") (class "Default")
      (node (ref "C15") (pin "2") (pinfunction "2_2") (pintype "passive"))
      (node (ref "C23") (pin "2") (pinfunction "2_2") (pintype "passive"))
      (node (ref "C24") (pin "2") (pinfunction "2_2") (pintype "passive"))
      (node (ref "R11") (pin "2") (pinfunction "2_2") (pintype "passive"))
      (node (ref "U10") (pin "1") (pinfunction "EN_1") (pintype "passive"))
      (node (ref "U10") (pin "4") (pinfunction "VIN_4") (pintype "passive"))
      (node (ref "U4") (pin "1") (pinfunction "VIN_1") (pintype "passive"))
      (node (ref "U8") (pin "1") (pinfunction "1_1") (pintype "passive"))
    )
    (net (code "19") (name "B+") (class "Default")
      (node (ref "C13") (pin "1") (pinfunction "1_1") (pintype "passive"))
      (node (ref "C7") (pin "2") (pinfunction "2_2") (pintype "passive"))
      (node (ref "C8") (pin "2") (pinfunction "2_2") (pintype "passive"))
      (node (ref "C9") (pin "2") (pinfunction "2_2") (pintype "passive"))
      (node (ref "Q1") (pin "3") (pinfunction "D_3") (pintype "passive"))
      (node (ref "R13") (pin "2") (pinfunction "2_2") (pintype "passive"))
      (node (ref "R7") (pin "1") (pinfunction "1_1") (pintype "passive"))
      (node (ref "SP3") (pin "1") (pinfunction "1_1") (pintype "passive"))
      (node (ref "U6") (pin "5") (pinfunction "BAT_5") (pintype "passive"))
    )
    (net (code "20") (name "B-") (class "Default")
      (node (ref "C13") (pin "2") (pinfunction "2_2") (pintype "passive"))
      (node (ref "C20") (pin "1") (pinfunction "1_1") (pintype "passive"))
      (node (ref "Q2") (pin "3") (pinfunction "S2_3") (pintype "passive"))
      (node (ref "SP4") (pin "1") (pinfunction "1_1") (pintype "passive"))
      (node (ref "U5") (pin "6") (pinfunction "GND_6") (pintype "passive"))
    )
    (net (code "21") (name "GND") (class "Default")
      (node (ref "C1") (pin "2") (pinfunction "2_2") (pintype "passive"))
      (node (ref "C11") (pin "1") (pinfunction "1_1") (pintype "passive"))
      (node (ref "C12") (pin "2") (pinfunction "2_2") (pintype "passive"))
      (node (ref "C14") (pin "1") (pinfunction "1_1") (pintype "passive"))
      (node (ref "C15") (pin "1") (pinfunction "1_1") (pintype "passive"))
      (node (ref "C16") (pin "1") (pinfunction "1_1") (pintype "passive"))
      (node (ref "C17") (pin "1") (pinfunction "1_1") (pintype "passive"))
      (node (ref "C18") (pin "1") (pinfunction "1_1") (pintype "passive"))
      (node (ref "C19") (pin "1") (pinfunction "1_1") (pintype "passive"))
      (node (ref "C2") (pin "1") (pinfunction "1_1") (pintype "passive"))
      (node (ref "C21") (pin "1") (pinfunction "1_1") (pintype "passive"))
      (node (ref "C22") (pin "1") (pinfunction "1_1") (pintype "passive"))
      (node (ref "C23") (pin "1") (pinfunction "1_1") (pintype "passive"))
      (node (ref "C24") (pin "1") (pinfunction "1_1") (pintype "passive"))
      (node (ref "C25") (pin "1") (pinfunction "1_1") (pintype "passive"))
      (node (ref "C26") (pin "1") (pinfunction "1_1") (pintype "passive"))
      (node (ref "C27") (pin "1") (pinfunction "1_1") (pintype "passive"))
      (node (ref "C28") (pin "1") (pinfunction "1_1") (pintype "passive"))
      (node (ref "C3") (pin "1") (pinfunction "1_1") (pintype "passive"))
      (node (ref "C4") (pin "1") (pinfunction "1_1") (pintype "passive"))
      (node (ref "C5") (pin "1") (pinfunction "1_1") (pintype "passive"))
      (node (ref "C7") (pin "1") (pinfunction "1_1") (pintype "passive"))
      (node (ref "C8") (pin "1") (pinfunction "1_1") (pintype "passive"))
      (node (ref "C9") (pin "1") (pinfunction "1_1") (pintype "passive"))
      (node (ref "JP1") (pin "A1") (pinfunction "GND_A1") (pintype "passive"))
      (node (ref "JP1") (pin "S1") (pinfunction "SHIELD_S1") (pintype "passive"))
      (node (ref "JP2") (pin "1") (pinfunction "1_1") (pintype "passive"))
      (node (ref "JP3") (pin "1") (pinfunction "1_1") (pintype "passive"))
      (node (ref "Q2") (pin "1") (pinfunction "S1_1") (pintype "passive"))
      (node (ref "R1") (pin "2") (pinfunction "2_2") (pintype "passive"))
      (node (ref "R10") (pin "2") (pinfunction "2_2") (pintype "passive"))
      (node (ref "R12") (pin "1") (pinfunction "1_1") (pintype "passive"))
      (node (ref "R16") (pin "1") (pinfunction "1_1") (pintype "passive"))
      (node (ref "R17") (pin "1") (pinfunction "1_1") (pintype "passive"))
      (node (ref "R19") (pin "1") (pinfunction "1_1") (pintype "passive"))
      (node (ref "R2") (pin "2") (pinfunction "2_2") (pintype "passive"))
      (node (ref "R5") (pin "1") (pinfunction "1_1") (pintype "passive"))
      (node (ref "R6") (pin "2") (pinfunction "2_2") (pintype "passive"))
      (node (ref "R8") (pin "2") (pinfunction "2_2") (pintype "passive"))
      (node (ref "SW1") (pin "3") (pinfunction "3_3") (pintype "passive"))
      (node (ref "SW2") (pin "1") (pinfunction "1_1") (pintype "passive"))
      (node (ref "SW3") (pin "1") (pinfunction "1_1") (pintype "passive"))
      (node (ref "SW4") (pin "1") (pinfunction "1_1") (pintype "passive"))
      (node (ref "U1") (pin "11") (pinfunction "EPAD_-_GND_11") (pintype "passive"))
      (node (ref "U10") (pin "2") (pinfunction "GND_2") (pintype "passive"))
      (node (ref "U3") (pin "4") (pinfunction "GND_4") (pintype "passive"))
      (node (ref "U4") (pin "2") (pinfunction "GND_2") (pintype "passive"))
      (node (ref "U6") (pin "1") (pinfunction "TEMP_1") (pintype "passive"))
      (node (ref "U6") (pin "3") (pinfunction "GND_3") (pintype "passive"))
      (node (ref "U6") (pin "9") (pinfunction "GND_9") (pintype "passive"))
      (node (ref "U7") (pin "2") (pinfunction "GND_2") (pintype "passive"))
      (node (ref "U9") (pin "15") (pinfunction "GND_15") (pintype "passive"))
    )
    (net (code "22") (name "Net-(C10-Pad2)") (class "Default")
      (node (ref "C10") (pin "2") (pinfunction "2_2") (pintype "passive"))
      (node (ref "R3") (pin "1") (pinfunction "1_1") (pintype "passive"))
    )
    (net (code "23") (name "Net-(C11-Pad2)") (class "Default")
      (node (ref "C11") (pin "2") (pinfunction "2_2") (pintype "passive"))
      (node (ref "R4") (pin "1") (pinfunction "1_1") (pintype "passive"))
    )
    (net (code "24") (name "Net-(D1-Pad2)") (class "Default")
      (node (ref "D1") (pin "2") (pinfunction "2_2") (pintype "passive"))
      (node (ref "R9") (pin "2") (pinfunction "2_2") (pintype "passive"))
    )
    (net (code "25") (name "Net-(D2-Pad1)") (class "Default")
      (node (ref "D2") (pin "1") (pinfunction "1_1") (pintype "passive"))
      (node (ref "R22") (pin "1") (pinfunction "1_1") (pintype "passive"))
    )
    (net (code "26") (name "Net-(JP1-CC1)") (class "Default")
      (node (ref "JP1") (pin "A5") (pinfunction "CC1_A5") (pintype "passive"))
      (node (ref "R1") (pin "1") (pinfunction "1_1") (pintype "passive"))
    )
    (net (code "27") (name "Net-(JP1-CC2)") (class "Default")
      (node (ref "JP1") (pin "B5") (pinfunction "CC2_B5") (pintype "passive"))
      (node (ref "R2") (pin "1") (pinfunction "1_1") (pintype "passive"))
    )
    (net (code "28") (name "Net-(Q1-S)") (class "Default")
      (node (ref "Q1") (pin "2") (pinfunction "S_2") (pintype "passive"))
      (node (ref "SW1") (pin "1") (pinfunction "1_1") (pintype "passive"))
      (node (ref "U2") (pin "1") (pinfunction "1_1") (pintype "passive"))
    )
    (net (code "29") (name "Net-(Q2-G1)") (class "Default")
      (node (ref "Q2") (pin "6") (pinfunction "G1_6") (pintype "passive"))
      (node (ref "U5") (pin "3") (pinfunction "OC_3") (pintype "passive"))
    )
    (net (code "30") (name "Net-(Q2-G2)") (class "Default")
      (node (ref "Q2") (pin "4") (pinfunction "G2_4") (pintype "passive"))
      (node (ref "U5") (pin "1") (pinfunction "OD_1") (pintype "passive"))
    )
    (net (code "31") (name "Net-(U1-CN)") (class "Default")
      (node (ref "C6") (pin "1") (pinfunction "1_1") (pintype "passive"))
      (node (ref "U1") (pin "3") (pinfunction "CN_3") (pintype "passive"))
    )
    (net (code "32") (name "Net-(U1-CP)") (class "Default")
      (node (ref "C6") (pin "2") (pinfunction "2_2") (pintype "passive"))
      (node (ref "U1") (pin "2") (pinfunction "CP_2") (pintype "passive"))
    )
    (net (code "33") (name "Net-(U1-CPOUT)") (class "Default")
      (node (ref "C1") (pin "1") (pinfunction "1_1") (pintype "passive"))
      (node (ref "C2") (pin "2") (pinfunction "2_2") (pintype "passive"))
      (node (ref "U1") (pin "10") (pinfunction "CPOUT_10") (pintype "passive"))
    )
    (net (code "34") (name "Net-(U1-INN)") (class "Default")
      (node (ref "R4") (pin "2") (pinfunction "2_2") (pintype "passive"))
      (node (ref "U1") (pin "7") (pinfunction "INN_7") (pintype "passive"))
    )
    (net (code "35") (name "Net-(U1-INP)") (class "Default")
      (node (ref "R3") (pin "2") (pinfunction "2_2") (pintype "passive"))
      (node (ref "U1") (pin "6") (pinfunction "INP_6") (pintype "passive"))
    )
    (net (code "36") (name "Net-(U4-BP)") (class "Default")
      (node (ref "C17") (pin "2") (pinfunction "2_2") (pintype "passive"))
      (node (ref "U4") (pin "4") (pinfunction "BP_4") (pintype "passive"))
    )
    (net (code "37") (name "Net-(U5-CS)") (class "Default")
      (node (ref "R8") (pin "1") (pinfunction "1_1") (pintype "passive"))
      (node (ref "U5") (pin "2") (pinfunction "CS_2") (pintype "passive"))
    )
    (net (code "38") (name "Net-(U5-VCC)") (class "Default")
      (node (ref "C20") (pin "2") (pinfunction "2_2") (pintype "passive"))
      (node (ref "R7") (pin "2") (pinfunction "2_2") (pintype "passive"))
      (node (ref "U5") (pin "5") (pinfunction "VCC_5") (pintype "passive"))
    )
    (net (code "39") (name "Net-(U6-PROG)") (class "Default")
      (node (ref "R10") (pin "1") (pinfunction "1_1") (pintype "passive"))
      (node (ref "U6") (pin "2") (pinfunction "PROG_2") (pintype "passive"))
    )
    (net (code "40") (name "Net-(U6-~{CHARG})") (class "Default")
      (node (ref "R9") (pin "1") (pinfunction "1_1") (pintype "passive"))
      (node (ref "U6") (pin "7") (pinfunction "~{CHARG}_7") (pintype "passive"))
    )
    (net (code "41") (name "Net-(U7-FB)") (class "Default")
      (node (ref "R11") (pin "1") (pinfunction "1_1") (pintype "passive"))
      (node (ref "R12") (pin "2") (pinfunction "2_2") (pintype "passive"))
      (node (ref "U7") (pin "3") (pinfunction "FB_3") (pintype "passive"))
    )
    (net (code "42") (name "Net-(U7-SW)") (class "Default")
      (node (ref "L1") (pin "2") (pinfunction "2_2") (pintype "passive"))
      (node (ref "U7") (pin "1") (pinfunction "SW_1") (pintype "passive"))
      (node (ref "U8") (pin "2") (pinfunction "2_2") (pintype "passive"))
    )
    (net (code "43") (name "Net-(U9-ADC)") (class "Default")
      (node (ref "R13") (pin "1") (pinfunction "1_1") (pintype "passive"))
      (node (ref "R16") (pin "2") (pinfunction "2_2") (pintype "passive"))
      (node (ref "U9") (pin "2") (pinfunction "ADC_2") (pintype "passive"))
    )
    (net (code "44") (name "Net-(U9-EN)") (class "Default")
      (node (ref "R14") (pin "2") (pinfunction "2_2") (pintype "passive"))
      (node (ref "U9") (pin "3") (pinfunction "EN_3") (pintype "passive"))
    )
    (net (code "45") (name "Net-(U9-VCC)") (class "Default")
      (node (ref "L2") (pin "1") (pinfunction "1_1") (pintype "passive"))
      (node (ref "U9") (pin "8") (pinfunction "VCC_8") (pintype "passive"))
    )
    (net (code "46") (name "Net-(U10-FB)") (class "Default")
      (node (ref "R18") (pin "1") (pinfunction "1_1") (pintype "passive"))
      (node (ref "R19") (pin "2") (pinfunction "2_2") (pintype "passive"))
      (node (ref "U10") (pin "5") (pinfunction "FB_5") (pintype "passive"))
    )
    (net (code "47") (name "Net-(U10-SW)") (class "Default")
      (node (ref "L3") (pin "1") (pinfunction "1_1") (pintype "passive"))
      (node (ref "U10") (pin "3") (pinfunction "SW_3") (pintype "passive"))
    )
    (net (code "48") (name "V_usb") (class "Default")
      (node (ref "C21") (pin "2") (pinfunction "2_2") (pintype "passive"))
      (node (ref "C22") (pin "2") (pinfunction "2_2") (pintype "passive"))
      (node (ref "C3") (pin "2") (pinfunction "2_2") (pintype "passive"))
      (node (ref "C4") (pin "2") (pinfunction "2_2") (pintype "passive"))
      (node (ref "C5") (pin "2") (pinfunction "2_2") (pintype "passive"))
      (node (ref "L1") (pin "1") (pinfunction "1_1") (pintype "passive"))
      (node (ref "SW1") (pin "2") (pinfunction "2_2") (pintype "passive"))
      (node (ref "U1") (pin "1") (pinfunction "VDD_1") (pintype "passive"))
      (node (ref "U1") (pin "5") (pinfunction "AVDD_5") (pintype "passive"))
      (node (ref "U7") (pin "4") (pinfunction "EN_4") (pintype "passive"))
      (node (ref "U7") (pin "5") (pinfunction "VIN_5") (pintype "passive"))
    )
    (net (code "49") (name "Vin") (class "Default")
      (node (ref "C12") (pin "1") (pinfunction "1_1") (pintype "passive"))
      (node (ref "D1") (pin "1") (pinfunction "1_1") (pintype "passive"))
      (node (ref "JP1") (pin "A4") (pinfunction "VBUS_A4") (pintype "passive"))
      (node (ref "Q1") (pin "1") (pinfunction "G_1") (pintype "passive"))
      (node (ref "R6") (pin "1") (pinfunction "1_1") (pintype "passive"))
      (node (ref "U2") (pin "2") (pinfunction "2_2") (pintype "passive"))
      (node (ref "U6") (pin "4") (pinfunction "VCC_4") (pintype "passive"))
      (node (ref "U6") (pin "8") (pinfunction "CE_8") (pintype "passive"))
    )
    (net (code "50") (name "unconnected-(JP1-D+-PadA6)") (class "Default")
      (node (ref "JP1") (pin "A6") (pinfunction "D+_A6") (pintype "passive"))
    )
    (net (code "51") (name "unconnected-(JP1-D+-PadB6)") (class "Default")
      (node (ref "JP1") (pin "B6") (pinfunction "D+_B6") (pintype "passive"))
    )
    (net (code "52") (name "unconnected-(JP1-D--PadA7)") (class "Default")
      (node (ref "JP1") (pin "A7") (pinfunction "D-_A7") (pintype "passive"))
    )
    (net (code "53") (name "unconnected-(JP1-D--PadB7)") (class "Default")
      (node (ref "JP1") (pin "B7") (pinfunction "D-_B7") (pintype "passive"))
    )
    (net (code "54") (name "unconnected-(JP1-SBU1-PadA8)") (class "Default")
      (node (ref "JP1") (pin "A8") (pinfunction "SBU1_A8") (pintype "passive"))
    )
    (net (code "55") (name "unconnected-(JP1-SBU2-PadB8)") (class "Default")
      (node (ref "JP1") (pin "B8") (pinfunction "SBU2_B8") (pintype "passive"))
    )
    (net (code "56") (name "unconnected-(Q2-D1{slash}D2-Pad5)") (class "Default")
      (node (ref "Q2") (pin "5") (pinfunction "D1/D2_5") (pintype "passive+no_connect"))
    )
    (net (code "57") (name "unconnected-(SW2-Pad3)") (class "Default")
      (node (ref "SW2") (pin "3") (pinfunction "3_3") (pintype "passive+no_connect"))
    )
    (net (code "58") (name "unconnected-(SW2-Pad4)") (class "Default")
      (node (ref "SW2") (pin "4") (pinfunction "4_4") (pintype "passive+no_connect"))
    )
    (net (code "59") (name "unconnected-(SW3-Pad3)") (class "Default")
      (node (ref "SW3") (pin "3") (pinfunction "3_3") (pintype "passive+no_connect"))
    )
    (net (code "60") (name "unconnected-(SW3-Pad4)") (class "Default")
      (node (ref "SW3") (pin "4") (pinfunction "4_4") (pintype "passive+no_connect"))
    )
    (net (code "61") (name "unconnected-(SW4-Pad3)") (class "Default")
      (node (ref "SW4") (pin "3") (pinfunction "3_3") (pintype "passive+no_connect"))
    )
    (net (code "62") (name "unconnected-(SW4-Pad4)") (class "Default")
      (node (ref "SW4") (pin "4") (pinfunction "4_4") (pintype "passive+no_connect"))
    )
    (net (code "63") (name "unconnected-(U3-NC-Pad7)") (class "Default")
      (node (ref "U3") (pin "7") (pinfunction "NC_7") (pintype "passive+no_connect"))
    )
    (net (code "64") (name "unconnected-(U3-RCH-Pad8)") (class "Default")
      (node (ref "U3") (pin "8") (pinfunction "RCH_8") (pintype "passive+no_connect"))
    )
    (net (code "65") (name "unconnected-(U4-EN-Pad3)") (class "Default")
      (node (ref "U4") (pin "3") (pinfunction "EN_3") (pintype "passive+no_connect"))
    )
    (net (code "66") (name "unconnected-(U5-TD-Pad4)") (class "Default")
      (node (ref "U5") (pin "4") (pinfunction "TD_4") (pintype "passive+no_connect"))
    )
    (net (code "67") (name "unconnected-(U6-~{STDBY}-Pad6)") (class "Default")
      (node (ref "U6") (pin "6") (pinfunction "~{STDBY}_6") (pintype "passive+no_connect"))
    )
    (net (code "68") (name "unconnected-(U7-NC-Pad6)") (class "Default")
      (node (ref "U7") (pin "6") (pinfunction "NC_6") (pintype "passive+no_connect"))
    )
    (net (code "69") (name "unconnected-(U9-CS0-Pad9)") (class "Default")
      (node (ref "U9") (pin "9") (pinfunction "CS0_9") (pintype "passive"))
    )
    (net (code "70") (name "unconnected-(U9-IO9-Pad11)") (class "Default")
      (node (ref "U9") (pin "11") (pinfunction "IO9_11") (pintype "passive"))
    )
    (net (code "71") (name "unconnected-(U9-IO10-Pad12)") (class "Default")
      (node (ref "U9") (pin "12") (pinfunction "IO10_12") (pintype "passive"))
    )
    (net (code "72") (name "unconnected-(U9-MISO-Pad10)") (class "Default")
      (node (ref "U9") (pin "10") (pinfunction "MISO_10") (pintype "passive"))
    )
    (net (code "73") (name "unconnected-(U9-MOSI-Pad13)") (class "Default")
      (node (ref "U9") (pin "13") (pinfunction "MOSI_13") (pintype "passive"))
    )
    (net (code "74") (name "unconnected-(U9-SCLK-Pad14)") (class "Default")
      (node (ref "U9") (pin "14") (pinfunction "SCLK_14") (pintype "passive"))
    )
  )
)
